# HP8555A_A9.net
KiCad netlist of a schematic drawn in Altium Designer
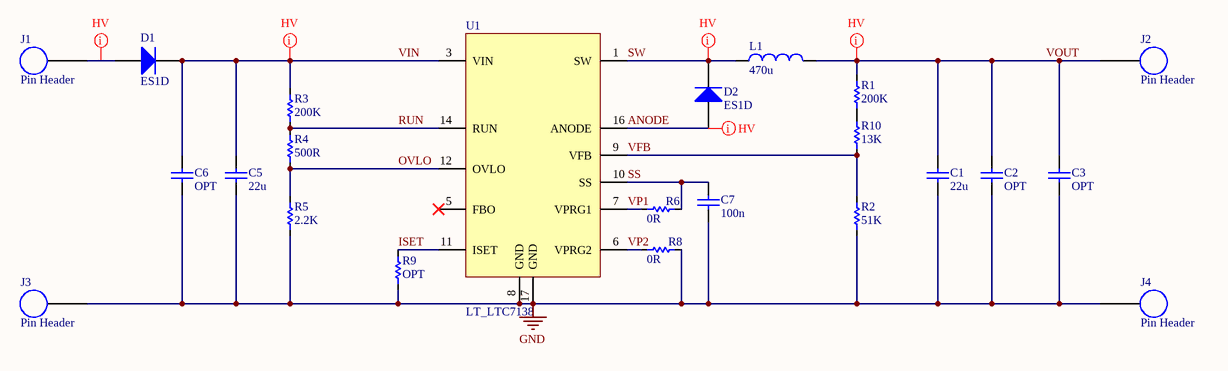
[diagram p0: HP8555A_A9.SchDoc]

(export (version "E")
  (design (tool "Eeschema 10.0.6"))
  (components
    (comp (ref "C1")
      (value "22u")
      (footprint "CAP_1210_M")
      (description "CAP Cnom Vcap Ptol Dial 1210")
      (fields (field (name "CREATED BY") "JS"))
      (libsource (lib "Passives") (part "CAP_1210"))
    )
    (comp (ref "C2")
      (value "OPT")
      (footprint "CAP_1210_M")
      (description "CAP Cnom Vcap Ptol Dial 1210")
      (fields (field (name "CREATED BY") "JS"))
      (libsource (lib "Passives") (part "CAP_1210"))
    )
    (comp (ref "C3")
      (value "OPT")
      (footprint "CAP_ALU_GEN")
      (description "CAP Cnom Vcap Ptol Dial")
      (fields (field (name "CREATED BY") "JS"))
      (libsource (lib "Passives") (part "CAP_ALU_GEN"))
    )
    (comp (ref "C5")
      (value "22u")
      (footprint "CAP_2220_M")
      (description "CAP Cnom Vcap Ptol Dial 2220")
      (fields (field (name "CREATED BY") "JS"))
      (libsource (lib "Passives") (part "CAP_2220"))
    )
    (comp (ref "C6")
      (value "OPT")
      (footprint "CAP_ALU_GEN")
      (description "CAP Cnom Vcap Ptol Dial")
      (fields (field (name "CREATED BY") "JS"))
      (libsource (lib "Passives") (part "CAP_ALU_GEN"))
    )
    (comp (ref "C7")
      (value "100n")
      (footprint "CAP_0603_M")
      (description "CAP 100nF Vcap Ptol Dial 0603")
      (fields (field (name "CREATED BY") "JS"))
      (libsource (lib "Passives") (part "CAP_0603"))
    )
    (comp (ref "D1")
      (value "ES1D")
      (footprint "Disc_Semi:ES1D")
      (description "DIODE 200V 1A SMA")
      (libsource (lib "Disc_Semi") (part "ES1D"))
    )
    (comp (ref "D2")
      (value "ES1D")
      (footprint "Disc_Semi:ES1D")
      (description "DIODE 200V 1A SMA")
      (libsource (lib "Disc_Semi") (part "ES1D"))
    )
    (comp (ref "J1")
      (value "Pin Header")
      (footprint "PIN_HEADER_1POS")
      (description "Pin Header 0.1\" 1pos")
      (libsource (lib "Connectors") (part "PIN_HEADER_1POS"))
    )
    (comp (ref "J2")
      (value "Pin Header")
      (footprint "PIN_HEADER_1POS")
      (description "Pin Header 0.1\" 1pos")
      (libsource (lib "Connectors") (part "PIN_HEADER_1POS"))
    )
    (comp (ref "J3")
      (value "Pin Header")
      (footprint "PIN_HEADER_1POS")
      (description "Pin Header 0.1\" 1pos")
      (libsource (lib "Connectors") (part "PIN_HEADER_1POS"))
    )
    (comp (ref "J4")
      (value "Pin Header")
      (footprint "PIN_HEADER_1POS")
      (description "Pin Header 0.1\" 1pos")
      (libsource (lib "Connectors") (part "PIN_HEADER_1POS"))
    )
    (comp (ref "L1")
      (value "470u")
      (footprint "TDK_SLF12555T")
      (description "IND Lind Ltol Imax Rdc")
      (libsource (lib "Passives") (part "TDK_SLF12555"))
    )
    (comp (ref "R1")
      (value "200K")
      (footprint "RES_0603_M")
      (description "RES OPT 1/5W 0805")
      (fields (field (name "CREATED BY") "JS"))
      (libsource (lib "Passives") (part "RES_0805"))
    )
    (comp (ref "R2")
      (value "51K")
      (footprint "RES_0603_M")
      (description "RES 51K 1/5W 0805")
      (fields (field (name "CREATED BY") "JS"))
      (libsource (lib "Passives") (part "RES_0805"))
    )
    (comp (ref "R3")
      (value "200K")
      (footprint "RES_0603_M")
      (description "RES 200K 1/5W 0805")
      (fields (field (name "CREATED BY") "JS"))
      (libsource (lib "Passives") (part "RES_0805"))
    )
    (comp (ref "R4")
      (value "500R")
      (footprint "RES_0603_M")
      (description "RES 500R 1/5W 0805")
      (fields (field (name "CREATED BY") "JS"))
      (libsource (lib "Passives") (part "RES_0805"))
    )
    (comp (ref "R5")
      (value "2.2K")
      (footprint "RES_0603_M")
      (description "RES 2.2K 1/5W 0805")
      (fields (field (name "CREATED BY") "JS"))
      (libsource (lib "Passives") (part "RES_0805"))
    )
    (comp (ref "R6")
      (value "0R")
      (footprint "RES_0603_M")
      (description "RES 0R 1/5W 0603")
      (fields (field (name "CREATED BY") "JS"))
      (libsource (lib "Passives") (part "RES_0603"))
    )
    (comp (ref "R8")
      (value "0R")
      (footprint "RES_0603_M")
      (description "RES 0R 1/5W 0603")
      (fields (field (name "CREATED BY") "JS"))
      (libsource (lib "Passives") (part "RES_0603"))
    )
    (comp (ref "R9")
      (value "OPT")
      (footprint "RES_0603_M")
      (description "RES OPT 1/5W 0603")
      (fields (field (name "CREATED BY") "JS"))
      (libsource (lib "Passives") (part "RES_0603"))
    )
    (comp (ref "R10")
      (value "13K")
      (footprint "RES_0603_M")
      (description "RES 13K 1/5W 0805")
      (fields (field (name "CREATED BY") "JS"))
      (libsource (lib "Passives") (part "RES_0805"))
    )
    (comp (ref "U1")
      (value "LT_LTC7138")
      (footprint "LT_LTC7138")
      (description "Step Down IC 140V 400mA")
      (fields (field (name "MANUFACTURER") "Linear Technology"))
      (libsource (lib "IC") (part "LT_LTC7138"))
    )
  )
  (nets
    (net (code "1") (name "/ANODE") (class "Default")
      (node (ref "D2") (pin "2") (pinfunction "A_2") (pintype "passive"))
      (node (ref "U1") (pin "16") (pinfunction "ANODE_16") (pintype "passive"))
    )
    (net (code "2") (name "/ISET") (class "Default")
      (node (ref "R9") (pin "2") (pinfunction "2_2") (pintype "passive"))
      (node (ref "U1") (pin "11") (pinfunction "ISET_11") (pintype "passive"))
    )
    (net (code "3") (name "/OVLO") (class "Default")
      (node (ref "R4") (pin "1") (pinfunction "1_1") (pintype "passive"))
      (node (ref "R5") (pin "2") (pinfunction "2_2") (pintype "passive"))
      (node (ref "U1") (pin "12") (pinfunction "OVLO_12") (pintype "passive"))
    )
    (net (code "4") (name "/RUN") (class "Default")
      (node (ref "R3") (pin "1") (pinfunction "1_1") (pintype "passive"))
      (node (ref "R4") (pin "2") (pinfunction "2_2") (pintype "passive"))
      (node (ref "U1") (pin "14") (pinfunction "RUN_14") (pintype "passive"))
    )
    (net (code "5") (name "/SS") (class "Default")
      (node (ref "C7") (pin "2") (pinfunction "2_2") (pintype "passive"))
      (node (ref "R6") (pin "2") (pinfunction "2_2") (pintype "passive"))
      (node (ref "U1") (pin "10") (pinfunction "SS_10") (pintype "passive"))
    )
    (net (code "6") (name "/SW") (class "Default")
      (node (ref "D2") (pin "1") (pinfunction "K_1") (pintype "passive"))
      (node (ref "L1") (pin "1") (pinfunction "1_1") (pintype "passive"))
      (node (ref "U1") (pin "1") (pinfunction "SW_1") (pintype "passive"))
    )
    (net (code "7") (name "/VFB") (class "Default")
      (node (ref "R10") (pin "1") (pinfunction "1_1") (pintype "passive"))
      (node (ref "R2") (pin "2") (pinfunction "2_2") (pintype "passive"))
      (node (ref "U1") (pin "9") (pinfunction "VFB_9") (pintype "passive"))
    )
    (net (code "8") (name "/VIN") (class "Default")
      (node (ref "C5") (pin "2") (pinfunction "2_2") (pintype "passive"))
      (node (ref "C6") (pin "2") (pinfunction "2_2") (pintype "passive"))
      (node (ref "D1") (pin "1") (pinfunction "K_1") (pintype "passive"))
      (node (ref "R3") (pin "2") (pinfunction "2_2") (pintype "passive"))
      (node (ref "U1") (pin "3") (pinfunction "VIN_3") (pintype "passive"))
    )
    (net (code "9") (name "/VOUT") (class "Default")
      (node (ref "C1") (pin "2") (pinfunction "2_2") (pintype "passive"))
      (node (ref "C2") (pin "2") (pinfunction "2_2") (pintype "passive"))
      (node (ref "C3") (pin "2") (pinfunction "2_2") (pintype "passive"))
      (node (ref "J2") (pin "1") (pinfunction "1_1") (pintype "passive"))
      (node (ref "L1") (pin "2") (pinfunction "2_2") (pintype "passive"))
      (node (ref "R1") (pin "2") (pinfunction "2_2") (pintype "passive"))
    )
    (net (code "10") (name "/VP1") (class "Default")
      (node (ref "R6") (pin "1") (pinfunction "1_1") (pintype "passive"))
      (node (ref "U1") (pin "7") (pinfunction "VPRG1_7") (pintype "passive"))
    )
    (net (code "11") (name "/VP2") (class "Default")
      (node (ref "R8") (pin "1") (pinfunction "1_1") (pintype "passive"))
      (node (ref "U1") (pin "6") (pinfunction "VPRG2_6") (pintype "passive"))
    )
    (net (code "12") (name "GND") (class "Default")
      (node (ref "C1") (pin "1") (pinfunction "1_1") (pintype "passive"))
      (node (ref "C2") (pin "1") (pinfunction "1_1") (pintype "passive"))
      (node (ref "C3") (pin "1") (pinfunction "1_1") (pintype "passive"))
      (node (ref "C5") (pin "1") (pinfunction "1_1") (pintype "passive"))
      (node (ref "C6") (pin "1") (pinfunction "1_1") (pintype "passive"))
      (node (ref "C7") (pin "1") (pinfunction "1_1") (pintype "passive"))
      (node (ref "J3") (pin "1") (pinfunction "1_1") (pintype "passive"))
      (node (ref "J4") (pin "1") (pinfunction "1_1") (pintype "passive"))
      (node (ref "R2") (pin "1") (pinfunction "1_1") (pintype "passive"))
      (node (ref "R5") (pin "1") (pinfunction "1_1") (pintype "passive"))
      (node (ref "R8") (pin "2") (pinfunction "2_2") (pintype "passive"))
      (node (ref "R9") (pin "1") (pinfunction "1_1") (pintype "passive"))
      (node (ref "U1") (pin "17") (pinfunction "GND_17") (pintype "passive"))
      (node (ref "U1") (pin "8") (pinfunction "GND_8") (pintype "passive"))
    )
    (net (code "13") (name "Net-(D1-A)") (class "Default")
      (node (ref "D1") (pin "2") (pinfunction "A_2") (pintype "passive"))
      (node (ref "J1") (pin "1") (pinfunction "1_1") (pintype "passive"))
    )
    (net (code "14") (name "Net-(R1-Pad1)") (class "Default")
      (node (ref "R1") (pin "1") (pinfunction "1_1") (pintype "passive"))
      (node (ref "R10") (pin "2") (pinfunction "2_2") (pintype "passive"))
    )
    (net (code "15") (name "unconnected-(U1-FBO-Pad5)") (class "Default")
      (node (ref "U1") (pin "5") (pinfunction "FBO_5") (pintype "passive+no_connect"))
    )
  )
)
